# Sayma_AMC.net
KiCad netlist of a schematic drawn in Altium Designer
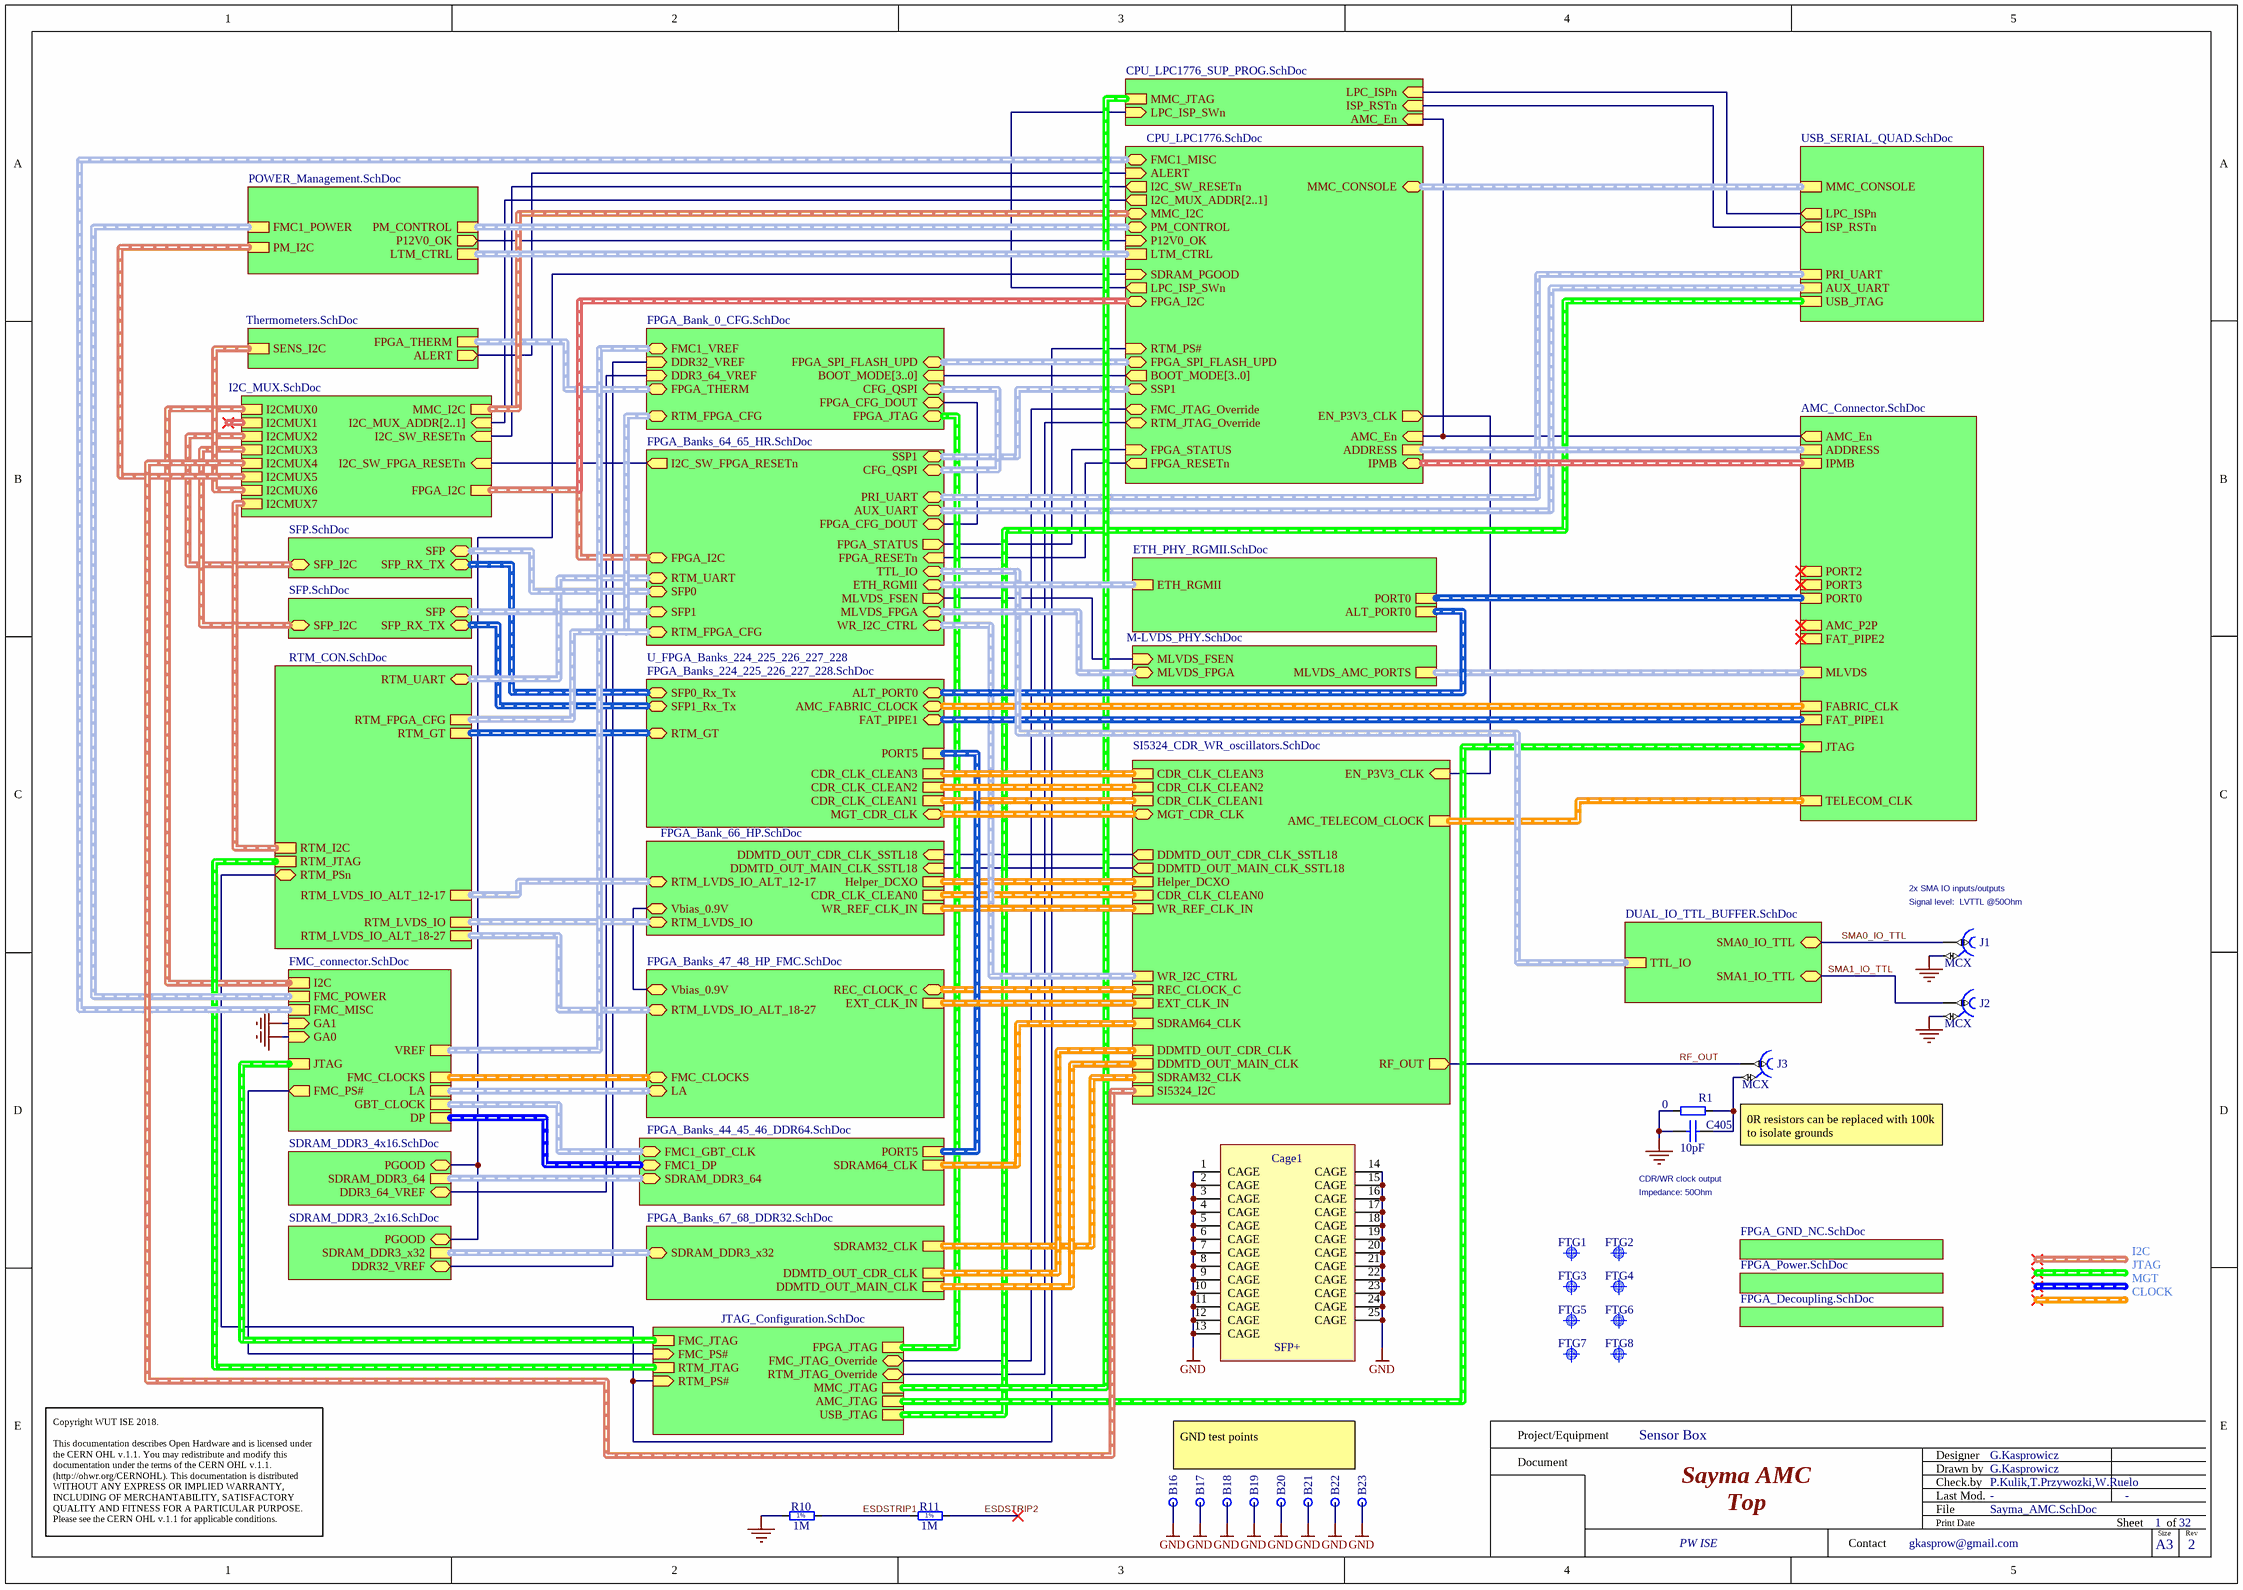
[diagram p0: Sayma_AMC.SchDoc]

(export (version "E")
  (design (tool "Eeschema 10.0.6"))
  (components
    (comp (ref "B16")
      (value "Plated Hole")
      (footprint "c130h80")
      (description "Single Terminal Socket")
      (fields (field (name "PART NUMBER") "PLATED_HOLE0.8_PAD1.3") (field (name "AUTHOR") "CERN DEM JLC"))
      (libsource (lib "Eletro-mechanical") (part "Single Terminal Socket"))
    )
    (comp (ref "B17")
      (value "Plated Hole")
      (footprint "c130h80")
      (description "Single Terminal Socket")
      (fields (field (name "PART NUMBER") "PLATED_HOLE0.8_PAD1.3") (field (name "AUTHOR") "CERN DEM JLC"))
      (libsource (lib "Eletro-mechanical") (part "Single Terminal Socket"))
    )
    (comp (ref "B18")
      (value "Plated Hole")
      (footprint "c130h80")
      (description "Single Terminal Socket")
      (fields (field (name "PART NUMBER") "PLATED_HOLE0.8_PAD1.3") (field (name "AUTHOR") "CERN DEM JLC"))
      (libsource (lib "Eletro-mechanical") (part "Single Terminal Socket"))
    )
    (comp (ref "B19")
      (value "Plated Hole")
      (footprint "c130h80")
      (description "Single Terminal Socket")
      (fields (field (name "PART NUMBER") "PLATED_HOLE0.8_PAD1.3") (field (name "AUTHOR") "CERN DEM JLC"))
      (libsource (lib "Eletro-mechanical") (part "Single Terminal Socket"))
    )
    (comp (ref "B20")
      (value "Plated Hole")
      (footprint "c130h80")
      (description "Single Terminal Socket")
      (fields (field (name "PART NUMBER") "PLATED_HOLE0.8_PAD1.3") (field (name "AUTHOR") "CERN DEM JLC"))
      (libsource (lib "Eletro-mechanical") (part "Single Terminal Socket"))
    )
    (comp (ref "B21")
      (value "Plated Hole")
      (footprint "c130h80")
      (description "Single Terminal Socket")
      (fields (field (name "PART NUMBER") "PLATED_HOLE0.8_PAD1.3") (field (name "AUTHOR") "CERN DEM JLC"))
      (libsource (lib "Eletro-mechanical") (part "Single Terminal Socket"))
    )
    (comp (ref "B22")
      (value "Plated Hole")
      (footprint "c130h80")
      (description "Single Terminal Socket")
      (fields (field (name "PART NUMBER") "PLATED_HOLE0.8_PAD1.3") (field (name "AUTHOR") "CERN DEM JLC"))
      (libsource (lib "Eletro-mechanical") (part "Single Terminal Socket"))
    )
    (comp (ref "B23")
      (value "Plated Hole")
      (footprint "c130h80")
      (description "Single Terminal Socket")
      (fields (field (name "PART NUMBER") "PLATED_HOLE0.8_PAD1.3") (field (name "AUTHOR") "CERN DEM JLC"))
      (libsource (lib "Eletro-mechanical") (part "Single Terminal Socket"))
    )
    (comp (ref "C405")
      (value "10pF")
      (footprint "CAPC1608X87N")
      (description "Non-polarised capacitor")
      (fields
        (field (name "MANUFACTURER PART NUMBER") "CC0603_10PF_50V_5%_NP0")
        (field (name "MANUFACTURER") "GENERIC")
        (field (name "AUTHOR") "CERN DEM JLC")
      )
      (libsource (lib "Capacitors") (part "Capacitor - non polarized"))
    )
    (comp (ref "Cage1")
      (value "SFP+")
      (footprint "TYCO_2007263-1")
      (description "SFP 1x2 Cage (25Pins)")
      (fields
        (field (name "PART NUMBER") "TYCO_2007263-1")
        (field (name "MANUFACTURER") "TYCO ELECTRONICS")
        (field (name "AUTHOR") "CERN DEM JLC")
      )
      (libsource (lib "Connectors") (part "SFP 1x2 Cage (25Pins)"))
    )
    (comp (ref "FTG1")
      (value "Use only in PCB")
      (footprint "FIDUCIAL_TOP_C100-200")
      (description "Fiducial Target")
      (fields (field (name "PART NUMBER") "FIDUCIAL_TARGET_C100-200") (field (name "AUTHOR") "CERN DEM JLC"))
      (libsource (lib "Eletro-mechanical") (part "Fiducial Target"))
    )
    (comp (ref "FTG2")
      (value "Use only in PCB")
      (footprint "FIDUCIAL_TOP_S100-200")
      (description "Fiducial Target")
      (fields (field (name "PART NUMBER") "FIDUCIAL_TARGET_S100-200") (field (name "AUTHOR") "CERN DEM JLC"))
      (libsource (lib "Eletro-mechanical") (part "Fiducial Target"))
    )
    (comp (ref "FTG3")
      (value "Use only in PCB")
      (footprint "FIDUCIAL_TOP_C100-200")
      (description "Fiducial Target")
      (fields (field (name "PART NUMBER") "FIDUCIAL_TARGET_C100-200") (field (name "AUTHOR") "CERN DEM JLC"))
      (libsource (lib "Eletro-mechanical") (part "Fiducial Target"))
    )
    (comp (ref "FTG4")
      (value "Use only in PCB")
      (footprint "FIDUCIAL_TOP_S100-200")
      (description "Fiducial Target")
      (fields (field (name "PART NUMBER") "FIDUCIAL_TARGET_S100-200") (field (name "AUTHOR") "CERN DEM JLC"))
      (libsource (lib "Eletro-mechanical") (part "Fiducial Target"))
    )
    (comp (ref "FTG5")
      (value "Use only in PCB")
      (footprint "FIDUCIAL_TOP_C100-200")
      (description "Fiducial Target")
      (fields (field (name "PART NUMBER") "FIDUCIAL_TARGET_C100-200") (field (name "AUTHOR") "CERN DEM JLC"))
      (libsource (lib "Eletro-mechanical") (part "Fiducial Target"))
    )
    (comp (ref "FTG6")
      (value "Use only in PCB")
      (footprint "FIDUCIAL_TOP_S100-200")
      (description "Fiducial Target")
      (fields (field (name "PART NUMBER") "FIDUCIAL_TARGET_S100-200") (field (name "AUTHOR") "CERN DEM JLC"))
      (libsource (lib "Eletro-mechanical") (part "Fiducial Target"))
    )
    (comp (ref "FTG7")
      (value "Use only in PCB")
      (footprint "FIDUCIAL_TOP_C100-200")
      (description "Fiducial Target")
      (fields (field (name "PART NUMBER") "FIDUCIAL_TARGET_C100-200") (field (name "AUTHOR") "CERN DEM JLC"))
      (libsource (lib "Eletro-mechanical") (part "Fiducial Target"))
    )
    (comp (ref "FTG8")
      (value "Use only in PCB")
      (footprint "FIDUCIAL_TOP_S100-200")
      (description "Fiducial Target")
      (fields (field (name "PART NUMBER") "FIDUCIAL_TARGET_S100-200") (field (name "AUTHOR") "CERN DEM JLC"))
      (libsource (lib "Eletro-mechanical") (part "Fiducial Target"))
    )
    (comp (ref "J1")
      (value "MCX")
      (footprint "AMPHENOL_ARF2521-ND")
      (fields
        (field (name "PART NUMBER") "AMPHENOL_ARF2521-ND")
        (field (name "MANUFACTURER") "AMPHENOL")
        (field (name "AUTHOR") "GK")
      )
      (libsource (lib "LIBRARY_SCH") (part "CON_MCX"))
    )
    (comp (ref "J2")
      (value "MCX")
      (footprint "AMPHENOL_ARF2521-ND")
      (fields
        (field (name "PART NUMBER") "AMPHENOL_ARF2521-ND")
        (field (name "MANUFACTURER") "AMPHENOL")
        (field (name "AUTHOR") "GK")
      )
      (libsource (lib "LIBRARY_SCH") (part "CON_MCX"))
    )
    (comp (ref "J3")
      (value "MCX")
      (footprint "AMPHENOL_ARF2521-ND")
      (fields
        (field (name "PART NUMBER") "AMPHENOL_ARF2521-ND")
        (field (name "MANUFACTURER") "AMPHENOL")
        (field (name "AUTHOR") "GK")
      )
      (libsource (lib "LIBRARY_SCH") (part "CON_MCX"))
    )
    (comp (ref "R1")
      (value "0")
      (footprint "RESC1005X40N")
      (description "Resistor")
      (fields
        (field (name "MANUFACTURER PART NUMBER") "R0402_0R_JUMPER")
        (field (name "MANUFACTURER") "GENERIC")
        (field (name "AUTHOR") "CERN DEM JLC")
      )
      (libsource (lib "Resistors") (part "Resistor"))
    )
    (comp (ref "R10")
      (value "1M")
      (footprint "RESC5025X65N")
      (description "Resistor - 1%")
      (fields
        (field (name "MANUFACTURER PART NUMBER") "R2010_1M_1%_0.5W_200PPM")
        (field (name "MANUFACTURER") "GENERIC")
        (field (name "AUTHOR") "CERN DEM JLC")
      )
      (libsource (lib "Resistors") (part "Resistor - 1%"))
    )
    (comp (ref "R11")
      (value "1M")
      (footprint "RESC5025X65N")
      (description "Resistor - 1%")
      (fields
        (field (name "MANUFACTURER PART NUMBER") "R2010_1M_1%_0.5W_200PPM")
        (field (name "MANUFACTURER") "GENERIC")
        (field (name "AUTHOR") "CERN DEM JLC")
      )
      (libsource (lib "Resistors") (part "Resistor - 1%"))
    )
  )
  (nets
    (net (code "24") (name "/ESDSTRIP1") (class "Default")
      (node (ref "R10") (pin "2") (pinfunction "2_2") (pintype "passive"))
      (node (ref "R11") (pin "1") (pinfunction "1_1") (pintype "passive"))
    )
    (net (code "25") (name "/ESDSTRIP2") (class "Default")
      (node (ref "R11") (pin "2") (pinfunction "2_2") (pintype "passive+no_connect"))
    )
    (net (code "79") (name "/RF_OUT") (class "Default")
      (node (ref "J3") (pin "1") (pinfunction "1_1") (pintype "bidirectional"))
    )
    (net (code "97") (name "/SMA0_IO_TTL") (class "Default")
      (node (ref "J1") (pin "1") (pinfunction "1_1") (pintype "bidirectional"))
    )
    (net (code "98") (name "/SMA1_IO_TTL") (class "Default")
      (node (ref "J2") (pin "1") (pinfunction "1_1") (pintype "bidirectional"))
    )
    (net (code "105") (name "GND") (class "Default")
      (node (ref "B16") (pin "1") (pinfunction "1_1") (pintype "bidirectional"))
      (node (ref "B17") (pin "1") (pinfunction "1_1") (pintype "bidirectional"))
      (node (ref "B18") (pin "1") (pinfunction "1_1") (pintype "bidirectional"))
      (node (ref "B19") (pin "1") (pinfunction "1_1") (pintype "bidirectional"))
      (node (ref "B20") (pin "1") (pinfunction "1_1") (pintype "bidirectional"))
      (node (ref "B21") (pin "1") (pinfunction "1_1") (pintype "bidirectional"))
      (node (ref "B22") (pin "1") (pinfunction "1_1") (pintype "bidirectional"))
      (node (ref "B23") (pin "1") (pinfunction "1_1") (pintype "bidirectional"))
      (node (ref "C405") (pin "1") (pinfunction "1_1") (pintype "passive"))
      (node (ref "Cage1") (pin "1") (pinfunction "CAGE_1") (pintype "power_in"))
      (node (ref "Cage1") (pin "10") (pinfunction "CAGE_10") (pintype "power_in"))
      (node (ref "Cage1") (pin "11") (pinfunction "CAGE_11") (pintype "power_in"))
      (node (ref "Cage1") (pin "12") (pinfunction "CAGE_12") (pintype "power_in"))
      (node (ref "Cage1") (pin "13") (pinfunction "CAGE_13") (pintype "power_in"))
      (node (ref "Cage1") (pin "14") (pinfunction "CAGE_14") (pintype "power_in"))
      (node (ref "Cage1") (pin "15") (pinfunction "CAGE_15") (pintype "power_in"))
      (node (ref "Cage1") (pin "16") (pinfunction "CAGE_16") (pintype "power_in"))
      (node (ref "Cage1") (pin "17") (pinfunction "CAGE_17") (pintype "power_in"))
      (node (ref "Cage1") (pin "18") (pinfunction "CAGE_18") (pintype "power_in"))
      (node (ref "Cage1") (pin "19") (pinfunction "CAGE_19") (pintype "power_in"))
      (node (ref "Cage1") (pin "2") (pinfunction "CAGE_2") (pintype "power_in"))
      (node (ref "Cage1") (pin "20") (pinfunction "CAGE_20") (pintype "power_in"))
      (node (ref "Cage1") (pin "21") (pinfunction "CAGE_21") (pintype "power_in"))
      (node (ref "Cage1") (pin "22") (pinfunction "CAGE_22") (pintype "power_in"))
      (node (ref "Cage1") (pin "23") (pinfunction "CAGE_23") (pintype "power_in"))
      (node (ref "Cage1") (pin "24") (pinfunction "CAGE_24") (pintype "power_in"))
      (node (ref "Cage1") (pin "25") (pinfunction "CAGE_25") (pintype "power_in"))
      (node (ref "Cage1") (pin "3") (pinfunction "CAGE_3") (pintype "power_in"))
      (node (ref "Cage1") (pin "4") (pinfunction "CAGE_4") (pintype "power_in"))
      (node (ref "Cage1") (pin "5") (pinfunction "CAGE_5") (pintype "power_in"))
      (node (ref "Cage1") (pin "6") (pinfunction "CAGE_6") (pintype "power_in"))
      (node (ref "Cage1") (pin "7") (pinfunction "CAGE_7") (pintype "power_in"))
      (node (ref "Cage1") (pin "8") (pinfunction "CAGE_8") (pintype "power_in"))
      (node (ref "Cage1") (pin "9") (pinfunction "CAGE_9") (pintype "power_in"))
      (node (ref "J1") (pin "2") (pinfunction "2_2") (pintype "bidirectional"))
      (node (ref "J2") (pin "2") (pinfunction "2_2") (pintype "bidirectional"))
      (node (ref "R1") (pin "2") (pinfunction "2_2") (pintype "passive"))
      (node (ref "R10") (pin "1") (pinfunction "1_1") (pintype "passive"))
    )
    (net (code "106") (name "Net-(C405-Pad2)") (class "Default")
      (node (ref "C405") (pin "2") (pinfunction "2_2") (pintype "passive"))
      (node (ref "J3") (pin "2") (pinfunction "2_2") (pintype "bidirectional"))
      (node (ref "R1") (pin "1") (pinfunction "1_1") (pintype "passive"))
    )
  )
)
